# AVRController.net
KiCad netlist of a schematic drawn in Altium Designer
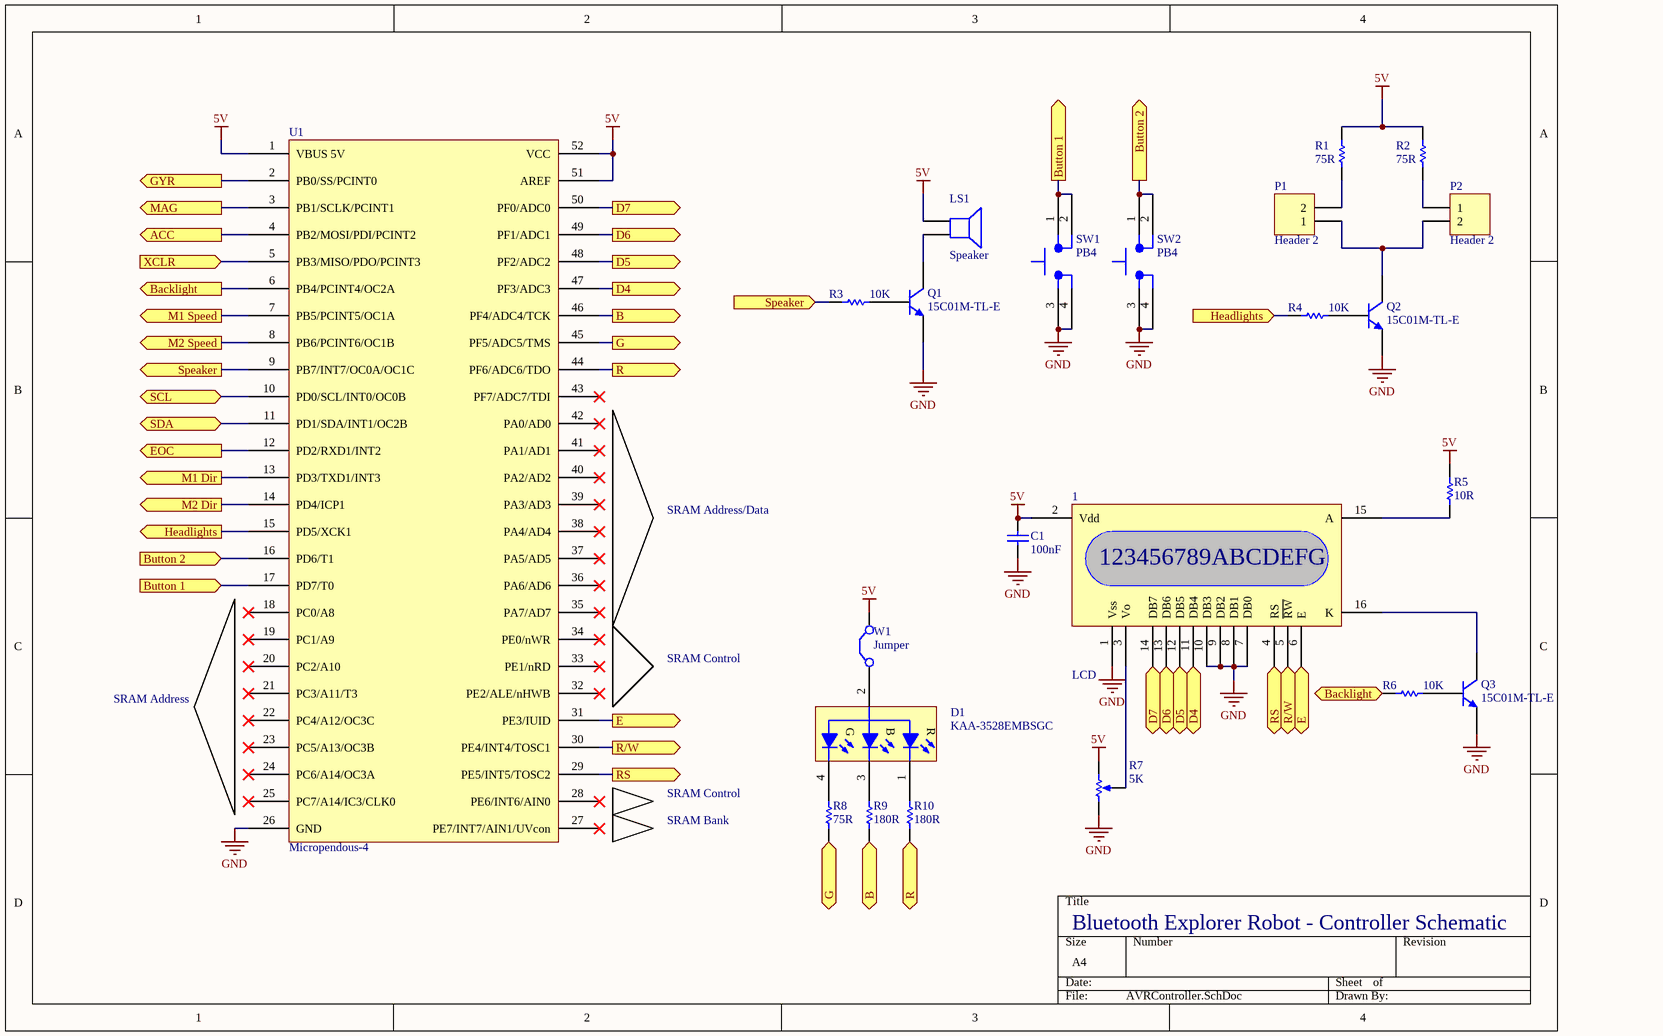
[diagram p0: AVRController.SchDoc]

(export (version "E")
  (design (tool "Eeschema 10.0.6"))
  (components
    (comp (ref "1") (value "LCD") (footprint "LCD_PADS") (libsource (lib "Latrobe") (part "LCD")))
    (comp (ref "C1")
      (value "100nF")
      (footprint "IPC-SM-782 Section 8.1 Chip Resistor:2012[0805]")
      (description "Capacitor (Semiconductor SIM Model)")
      (fields (field (name "PUBLISHER") "Altium Limited"))
      (libsource (lib "Miscellaneous Devices") (part "Cap Semi"))
    )
    (comp (ref "D1")
      (value "KAA-3528EMBSGC")
      (footprint "KAA-3528EMBSGC")
      (description "Ultra-Bright RGB Tri-color LED Lamp, 4-Lead 1204-size SMD")
      (fields (field (name "PUBLISHER") "Altium Limited"))
      (libsource (lib "Sansen Optoelectronic LED") (part "S1204RGBSDJC"))
    )
    (comp (ref "LS1")
      (value "Speaker")
      (footprint "PIN2")
      (description "Loudspeaker")
      (fields (field (name "PUBLISHER") "Altium Limited"))
      (libsource (lib "Miscellaneous Devices") (part "Speaker"))
    )
    (comp (ref "P1")
      (value "Header 2")
      (footprint "HDR1X2")
      (description "Header, 2-Pin")
      (fields (field (name "PUBLISHER") "Altium Limited"))
      (libsource (lib "Miscellaneous Connectors") (part "Header 2"))
    )
    (comp (ref "P2")
      (value "Header 2")
      (footprint "HDR1X2")
      (description "Header, 2-Pin")
      (fields (field (name "PUBLISHER") "Altium Limited"))
      (libsource (lib "") (part "Header 2_1"))
    )
    (comp (ref "Q1")
      (value "15C01M-TL-E")
      (footprint "SOT323")
      (description "NPN General Purpose Amplifier")
      (fields (field (name "PUBLISHER") "Altium Limited"))
      (libsource (lib "Miscellaneous Devices") (part "2N3904"))
    )
    (comp (ref "Q2")
      (value "15C01M-TL-E")
      (footprint "SOT323")
      (description "NPN General Purpose Amplifier")
      (fields (field (name "PUBLISHER") "Altium Limited"))
      (libsource (lib "Miscellaneous Devices") (part "2N3904"))
    )
    (comp (ref "Q3")
      (value "15C01M-TL-E")
      (footprint "SOT323")
      (description "NPN General Purpose Amplifier")
      (fields (field (name "PUBLISHER") "Altium Limited"))
      (libsource (lib "Miscellaneous Devices") (part "2N3904"))
    )
    (comp (ref "R1")
      (value "75R")
      (footprint "2012[0805]")
      (description "Semiconductor Resistor")
      (fields (field (name "Comment") "Res Semi") (field (name "PUBLISHER") "Altium Limited"))
      (libsource (lib "Miscellaneous Devices") (part "Res Semi"))
    )
    (comp (ref "R2")
      (value "75R")
      (footprint "2012[0805]")
      (description "Semiconductor Resistor")
      (fields (field (name "Comment") "Res Semi") (field (name "PUBLISHER") "Altium Limited"))
      (libsource (lib "Miscellaneous Devices") (part "Res Semi"))
    )
    (comp (ref "R3")
      (value "10K")
      (footprint "2012[0805]")
      (description "Semiconductor Resistor")
      (fields (field (name "Comment") "Res Semi") (field (name "PUBLISHER") "Altium Limited"))
      (libsource (lib "Miscellaneous Devices") (part "Res Semi"))
    )
    (comp (ref "R4")
      (value "10K")
      (footprint "2012[0805]")
      (description "Semiconductor Resistor")
      (fields (field (name "Comment") "Res Semi") (field (name "PUBLISHER") "Altium Limited"))
      (libsource (lib "Miscellaneous Devices") (part "Res Semi"))
    )
    (comp (ref "R5")
      (value "10R")
      (footprint "IPC-SM-782 Section 8.1 Chip Resistor:2012[0805]")
      (description "Resistor")
      (fields (field (name "PUBLISHER") "Altium Limited"))
      (libsource (lib "Miscellaneous Devices") (part "Res1"))
    )
    (comp (ref "R6")
      (value "10K")
      (footprint "2012[0805]")
      (description "Semiconductor Resistor")
      (fields (field (name "Comment") "Res Semi") (field (name "PUBLISHER") "Altium Limited"))
      (libsource (lib "Miscellaneous Devices") (part "Res Semi"))
    )
    (comp (ref "R7")
      (value "5K")
      (footprint "POT1")
      (description "Potentiometer")
      (fields (field (name "PUBLISHER") "Altium Limited"))
      (libsource (lib "Miscellaneous Devices") (part "RPot"))
    )
    (comp (ref "R8")
      (value "75R")
      (footprint "2012[0805]")
      (description "Semiconductor Resistor")
      (fields (field (name "Comment") "Res Semi") (field (name "PUBLISHER") "Altium Limited"))
      (libsource (lib "Miscellaneous Devices") (part "Res Semi"))
    )
    (comp (ref "R9")
      (value "180R")
      (footprint "2012[0805]")
      (description "Semiconductor Resistor")
      (fields (field (name "Comment") "Res Semi") (field (name "PUBLISHER") "Altium Limited"))
      (libsource (lib "Miscellaneous Devices") (part "Res Semi"))
    )
    (comp (ref "R10")
      (value "180R")
      (footprint "2012[0805]")
      (description "Semiconductor Resistor")
      (fields (field (name "Comment") "Res Semi") (field (name "PUBLISHER") "Altium Limited"))
      (libsource (lib "Miscellaneous Devices") (part "Res Semi"))
    )
    (comp (ref "SW1") (value "PB4") (footprint "PB2x2") (libsource (lib "Latrobe") (part "PB4")))
    (comp (ref "SW2") (value "PB4") (footprint "PB2x2") (libsource (lib "Latrobe") (part "PB4")))
    (comp (ref "U1")
      (value "Micropendous-4")
      (footprint "Micropendous-4")
      (libsource (lib "Micropendous") (part "Micropendous-4"))
    )
    (comp (ref "W1")
      (value "Jumper")
      (footprint "RAD-0.2")
      (description "Jumper Wire")
      (fields (field (name "PUBLISHER") "Altium Limited"))
      (libsource (lib "Miscellaneous Devices") (part "Jumper"))
    )
  )
  (nets
    (net (code "1") (name "/ACC") (class "Default")
      (node (ref "U1") (pin "4") (pinfunction "PB2/MOSI/PDI/PCINT2_4") (pintype "passive"))
    )
    (net (code "2") (name "/B") (class "Default")
      (node (ref "R9") (pin "1") (pinfunction "1_1") (pintype "passive"))
      (node (ref "U1") (pin "46") (pinfunction "PF4/ADC4/TCK_46") (pintype "passive"))
    )
    (net (code "3") (name "/Backlight") (class "Default")
      (node (ref "R6") (pin "1") (pinfunction "1_1") (pintype "passive"))
      (node (ref "U1") (pin "6") (pinfunction "PB4/PCINT4/OC2A_6") (pintype "passive"))
    )
    (net (code "4") (name "/Button 1") (class "Default")
      (node (ref "SW1") (pin "1") (pinfunction "1_1") (pintype "passive"))
      (node (ref "SW1") (pin "2") (pinfunction "2_2") (pintype "passive"))
      (node (ref "U1") (pin "17") (pinfunction "PD7/T0_17") (pintype "passive"))
    )
    (net (code "5") (name "/Button 2") (class "Default")
      (node (ref "SW2") (pin "1") (pinfunction "1_1") (pintype "passive"))
      (node (ref "SW2") (pin "2") (pinfunction "2_2") (pintype "passive"))
      (node (ref "U1") (pin "16") (pinfunction "PD6/T1_16") (pintype "passive"))
    )
    (net (code "6") (name "/D4") (class "Default")
      (node (ref "1") (pin "11") (pinfunction "DB4_11") (pintype "passive"))
      (node (ref "U1") (pin "47") (pinfunction "PF3/ADC3_47") (pintype "passive"))
    )
    (net (code "7") (name "/D5") (class "Default")
      (node (ref "1") (pin "12") (pinfunction "DB5_12") (pintype "passive"))
      (node (ref "U1") (pin "48") (pinfunction "PF2/ADC2_48") (pintype "passive"))
    )
    (net (code "8") (name "/D6") (class "Default")
      (node (ref "1") (pin "13") (pinfunction "DB6_13") (pintype "passive"))
      (node (ref "U1") (pin "49") (pinfunction "PF1/ADC1_49") (pintype "passive"))
    )
    (net (code "9") (name "/D7") (class "Default")
      (node (ref "1") (pin "14") (pinfunction "DB7_14") (pintype "passive"))
      (node (ref "U1") (pin "50") (pinfunction "PF0/ADC0_50") (pintype "passive"))
    )
    (net (code "10") (name "/E") (class "Default")
      (node (ref "1") (pin "6") (pinfunction "E_6") (pintype "passive"))
      (node (ref "U1") (pin "31") (pinfunction "PE3/IUID_31") (pintype "passive"))
    )
    (net (code "11") (name "/EOC") (class "Default")
      (node (ref "U1") (pin "12") (pinfunction "PD2/RXD1/INT2_12") (pintype "passive"))
    )
    (net (code "12") (name "/G") (class "Default")
      (node (ref "R8") (pin "1") (pinfunction "1_1") (pintype "passive"))
      (node (ref "U1") (pin "45") (pinfunction "PF5/ADC5/TMS_45") (pintype "passive"))
    )
    (net (code "13") (name "/GYR") (class "Default")
      (node (ref "U1") (pin "2") (pinfunction "PB0/SS/PCINT0_2") (pintype "passive"))
    )
    (net (code "14") (name "/Headlights") (class "Default")
      (node (ref "R4") (pin "1") (pinfunction "1_1") (pintype "passive"))
      (node (ref "U1") (pin "15") (pinfunction "PD5/XCK1_15") (pintype "passive"))
    )
    (net (code "15") (name "/M1 Dir") (class "Default")
      (node (ref "U1") (pin "13") (pinfunction "PD3/TXD1/INT3_13") (pintype "passive"))
    )
    (net (code "16") (name "/M1 Speed") (class "Default")
      (node (ref "U1") (pin "7") (pinfunction "PB5/PCINT5/OC1A_7") (pintype "passive"))
    )
    (net (code "17") (name "/M2 Dir") (class "Default")
      (node (ref "U1") (pin "14") (pinfunction "PD4/ICP1_14") (pintype "passive"))
    )
    (net (code "18") (name "/M2 Speed") (class "Default")
      (node (ref "U1") (pin "8") (pinfunction "PB6/PCINT6/OC1B_8") (pintype "passive"))
    )
    (net (code "19") (name "/MAG") (class "Default")
      (node (ref "U1") (pin "3") (pinfunction "PB1/SCLK/PCINT1_3") (pintype "passive"))
    )
    (net (code "20") (name "/R") (class "Default")
      (node (ref "R10") (pin "1") (pinfunction "1_1") (pintype "passive"))
      (node (ref "U1") (pin "44") (pinfunction "PF6/ADC6/TDO_44") (pintype "passive"))
    )
    (net (code "21") (name "/RS") (class "Default")
      (node (ref "1") (pin "4") (pinfunction "RS_4") (pintype "passive"))
      (node (ref "U1") (pin "29") (pinfunction "PE5/INT5/TOSC2_29") (pintype "passive"))
    )
    (net (code "22") (name "/R{slash}W") (class "Default")
      (node (ref "1") (pin "5") (pinfunction "~{RW}_5") (pintype "passive"))
      (node (ref "U1") (pin "30") (pinfunction "PE4/INT4/TOSC1_30") (pintype "passive"))
    )
    (net (code "23") (name "/SCL") (class "Default")
      (node (ref "U1") (pin "10") (pinfunction "PD0/SCL/INT0/OC0B_10") (pintype "passive"))
    )
    (net (code "24") (name "/SDA") (class "Default")
      (node (ref "U1") (pin "11") (pinfunction "PD1/SDA/INT1/OC2B_11") (pintype "passive"))
    )
    (net (code "25") (name "/Speaker") (class "Default")
      (node (ref "R3") (pin "1") (pinfunction "1_1") (pintype "passive"))
      (node (ref "U1") (pin "9") (pinfunction "PB7/INT7/OC0A/OC1C_9") (pintype "passive"))
    )
    (net (code "26") (name "/XCLR") (class "Default")
      (node (ref "U1") (pin "5") (pinfunction "PB3/MISO/PDO/PCINT3_5") (pintype "passive"))
    )
    (net (code "27") (name "5V") (class "Default")
      (node (ref "1") (pin "2") (pinfunction "Vdd_2") (pintype "passive"))
      (node (ref "C1") (pin "1") (pinfunction "1_1") (pintype "passive"))
      (node (ref "LS1") (pin "1") (pinfunction "1_1") (pintype "passive"))
      (node (ref "R1") (pin "2") (pinfunction "2_2") (pintype "passive"))
      (node (ref "R2") (pin "2") (pinfunction "2_2") (pintype "passive"))
      (node (ref "R5") (pin "2") (pinfunction "2_2") (pintype "passive"))
      (node (ref "R7") (pin "2") (pinfunction "BOT_2") (pintype "passive"))
      (node (ref "U1") (pin "1") (pinfunction "VBUS_5V_1") (pintype "passive"))
      (node (ref "U1") (pin "51") (pinfunction "AREF_51") (pintype "passive"))
      (node (ref "U1") (pin "52") (pinfunction "VCC_52") (pintype "passive"))
      (node (ref "W1") (pin "2") (pinfunction "C2_2") (pintype "passive"))
    )
    (net (code "28") (name "GND") (class "Default")
      (node (ref "1") (pin "1") (pinfunction "Vss_1") (pintype "passive"))
      (node (ref "1") (pin "10") (pinfunction "DB3_10") (pintype "passive"))
      (node (ref "1") (pin "7") (pinfunction "DB0_7") (pintype "passive"))
      (node (ref "1") (pin "8") (pinfunction "DB1_8") (pintype "passive"))
      (node (ref "1") (pin "9") (pinfunction "DB2_9") (pintype "passive"))
      (node (ref "C1") (pin "2") (pinfunction "2_2") (pintype "passive"))
      (node (ref "Q1") (pin "1") (pinfunction "E_1") (pintype "passive"))
      (node (ref "Q2") (pin "1") (pinfunction "E_1") (pintype "passive"))
      (node (ref "Q3") (pin "1") (pinfunction "E_1") (pintype "passive"))
      (node (ref "R7") (pin "1") (pinfunction "TOP_1") (pintype "passive"))
      (node (ref "SW1") (pin "3") (pinfunction "3_3") (pintype "passive"))
      (node (ref "SW1") (pin "4") (pinfunction "4_4") (pintype "passive"))
      (node (ref "SW2") (pin "3") (pinfunction "3_3") (pintype "passive"))
      (node (ref "SW2") (pin "4") (pinfunction "4_4") (pintype "passive"))
      (node (ref "U1") (pin "26") (pinfunction "GND_26") (pintype "passive"))
    )
    (net (code "29") (name "Net-(1-A)") (class "Default")
      (node (ref "1") (pin "15") (pinfunction "A_15") (pintype "passive"))
      (node (ref "R5") (pin "1") (pinfunction "1_1") (pintype "passive"))
    )
    (net (code "30") (name "Net-(1-K)") (class "Default")
      (node (ref "1") (pin "16") (pinfunction "K_16") (pintype "passive"))
      (node (ref "Q3") (pin "3") (pinfunction "C_3") (pintype "passive"))
    )
    (net (code "31") (name "Net-(1-Vo)") (class "Default")
      (node (ref "1") (pin "3") (pinfunction "Vo_3") (pintype "passive"))
      (node (ref "R7") (pin "3") (pinfunction "TAP_3") (pintype "passive"))
    )
    (net (code "32") (name "Net-(D1-A2)") (class "Default")
      (node (ref "D1") (pin "2") (pinfunction "A2_2") (pintype "passive"))
      (node (ref "W1") (pin "1") (pinfunction "C1_1") (pintype "passive"))
    )
    (net (code "33") (name "Net-(D1-B)") (class "Default")
      (node (ref "D1") (pin "3") (pinfunction "B_3") (pintype "passive"))
      (node (ref "R9") (pin "2") (pinfunction "2_2") (pintype "passive"))
    )
    (net (code "34") (name "Net-(D1-G)") (class "Default")
      (node (ref "D1") (pin "4") (pinfunction "G_4") (pintype "passive"))
      (node (ref "R8") (pin "2") (pinfunction "2_2") (pintype "passive"))
    )
    (net (code "35") (name "Net-(D1-R)") (class "Default")
      (node (ref "D1") (pin "1") (pinfunction "R_1") (pintype "passive"))
      (node (ref "R10") (pin "2") (pinfunction "2_2") (pintype "passive"))
    )
    (net (code "36") (name "Net-(P1-Pad2)") (class "Default")
      (node (ref "P1") (pin "2") (pinfunction "2_2") (pintype "passive"))
      (node (ref "R1") (pin "1") (pinfunction "1_1") (pintype "passive"))
    )
    (net (code "37") (name "Net-(P2-Pad1)") (class "Default")
      (node (ref "P2") (pin "1") (pinfunction "1_1") (pintype "passive"))
      (node (ref "R2") (pin "1") (pinfunction "1_1") (pintype "passive"))
    )
    (net (code "38") (name "Net-(Q1-B)") (class "Default")
      (node (ref "Q1") (pin "2") (pinfunction "B_2") (pintype "passive"))
      (node (ref "R3") (pin "2") (pinfunction "2_2") (pintype "passive"))
    )
    (net (code "39") (name "Net-(Q1-C)") (class "Default")
      (node (ref "LS1") (pin "2") (pinfunction "2_2") (pintype "passive"))
      (node (ref "Q1") (pin "3") (pinfunction "C_3") (pintype "passive"))
    )
    (net (code "40") (name "Net-(Q2-B)") (class "Default")
      (node (ref "Q2") (pin "2") (pinfunction "B_2") (pintype "passive"))
      (node (ref "R4") (pin "2") (pinfunction "2_2") (pintype "passive"))
    )
    (net (code "41") (name "Net-(Q2-C)") (class "Default")
      (node (ref "P1") (pin "1") (pinfunction "1_1") (pintype "passive"))
      (node (ref "P2") (pin "2") (pinfunction "2_2") (pintype "passive"))
      (node (ref "Q2") (pin "3") (pinfunction "C_3") (pintype "passive"))
    )
    (net (code "42") (name "Net-(Q3-B)") (class "Default")
      (node (ref "Q3") (pin "2") (pinfunction "B_2") (pintype "passive"))
      (node (ref "R6") (pin "2") (pinfunction "2_2") (pintype "passive"))
    )
    (net (code "43") (name "unconnected-(U1-PA0{slash}AD0-Pad42)") (class "Default")
      (node (ref "U1") (pin "42") (pinfunction "PA0/AD0_42") (pintype "passive+no_connect"))
    )
    (net (code "44") (name "unconnected-(U1-PA1{slash}AD1-Pad41)") (class "Default")
      (node (ref "U1") (pin "41") (pinfunction "PA1/AD1_41") (pintype "passive+no_connect"))
    )
    (net (code "45") (name "unconnected-(U1-PA2{slash}AD2-Pad40)") (class "Default")
      (node (ref "U1") (pin "40") (pinfunction "PA2/AD2_40") (pintype "passive+no_connect"))
    )
    (net (code "46") (name "unconnected-(U1-PA3{slash}AD3-Pad39)") (class "Default")
      (node (ref "U1") (pin "39") (pinfunction "PA3/AD3_39") (pintype "passive+no_connect"))
    )
    (net (code "47") (name "unconnected-(U1-PA4{slash}AD4-Pad38)") (class "Default")
      (node (ref "U1") (pin "38") (pinfunction "PA4/AD4_38") (pintype "passive+no_connect"))
    )
    (net (code "48") (name "unconnected-(U1-PA5{slash}AD5-Pad37)") (class "Default")
      (node (ref "U1") (pin "37") (pinfunction "PA5/AD5_37") (pintype "passive+no_connect"))
    )
    (net (code "49") (name "unconnected-(U1-PA6{slash}AD6-Pad36)") (class "Default")
      (node (ref "U1") (pin "36") (pinfunction "PA6/AD6_36") (pintype "passive+no_connect"))
    )
    (net (code "50") (name "unconnected-(U1-PA7{slash}AD7-Pad35)") (class "Default")
      (node (ref "U1") (pin "35") (pinfunction "PA7/AD7_35") (pintype "passive+no_connect"))
    )
    (net (code "51") (name "unconnected-(U1-PC0{slash}A8-Pad18)") (class "Default")
      (node (ref "U1") (pin "18") (pinfunction "PC0/A8_18") (pintype "passive+no_connect"))
    )
    (net (code "52") (name "unconnected-(U1-PC1{slash}A9-Pad19)") (class "Default")
      (node (ref "U1") (pin "19") (pinfunction "PC1/A9_19") (pintype "passive+no_connect"))
    )
    (net (code "53") (name "unconnected-(U1-PC2{slash}A10-Pad20)") (class "Default")
      (node (ref "U1") (pin "20") (pinfunction "PC2/A10_20") (pintype "passive+no_connect"))
    )
    (net (code "54") (name "unconnected-(U1-PC3{slash}A11{slash}T3-Pad21)") (class "Default")
      (node (ref "U1") (pin "21") (pinfunction "PC3/A11/T3_21") (pintype "passive+no_connect"))
    )
    (net (code "55") (name "unconnected-(U1-PC4{slash}A12{slash}OC3C-Pad22)") (class "Default")
      (node (ref "U1") (pin "22") (pinfunction "PC4/A12/OC3C_22") (pintype "passive+no_connect"))
    )
    (net (code "56") (name "unconnected-(U1-PC5{slash}A13{slash}OC3B-Pad23)") (class "Default")
      (node (ref "U1") (pin "23") (pinfunction "PC5/A13/OC3B_23") (pintype "passive+no_connect"))
    )
    (net (code "57") (name "unconnected-(U1-PC6{slash}A14{slash}OC3A-Pad24)") (class "Default")
      (node (ref "U1") (pin "24") (pinfunction "PC6/A14/OC3A_24") (pintype "passive+no_connect"))
    )
    (net (code "58") (name "unconnected-(U1-PC7{slash}A14{slash}IC3{slash}CLK0-Pad25)") (class "Default")
      (node (ref "U1") (pin "25") (pinfunction "PC7/A14/IC3/CLK0_25") (pintype "passive+no_connect"))
    )
    (net (code "59") (name "unconnected-(U1-PE0{slash}nWR-Pad34)") (class "Default")
      (node (ref "U1") (pin "34") (pinfunction "PE0/nWR_34") (pintype "passive+no_connect"))
    )
    (net (code "60") (name "unconnected-(U1-PE1{slash}nRD-Pad33)") (class "Default")
      (node (ref "U1") (pin "33") (pinfunction "PE1/nRD_33") (pintype "passive+no_connect"))
    )
    (net (code "61") (name "unconnected-(U1-PE2{slash}ALE{slash}nHWB-Pad32)") (class "Default")
      (node (ref "U1") (pin "32") (pinfunction "PE2/ALE/nHWB_32") (pintype "passive+no_connect"))
    )
    (net (code "62") (name "unconnected-(U1-PE6{slash}INT6{slash}AIN0-Pad28)") (class "Default")
      (node (ref "U1") (pin "28") (pinfunction "PE6/INT6/AIN0_28") (pintype "passive+no_connect"))
    )
    (net (code "63") (name "unconnected-(U1-PE7{slash}INT7{slash}AIN1{slash}UVcon-Pad27)") (class "Default")
      (node (ref "U1") (pin "27") (pinfunction "PE7/INT7/AIN1/UVcon_27") (pintype "passive+no_connect"))
    )
    (net (code "64") (name "unconnected-(U1-PF7{slash}ADC7{slash}TDI-Pad43)") (class "Default")
      (node (ref "U1") (pin "43") (pinfunction "PF7/ADC7/TDI_43") (pintype "passive+no_connect"))
    )
  )
)
